# CowHeater_SCH.net
KiCad netlist of a schematic drawn in Altium Designer
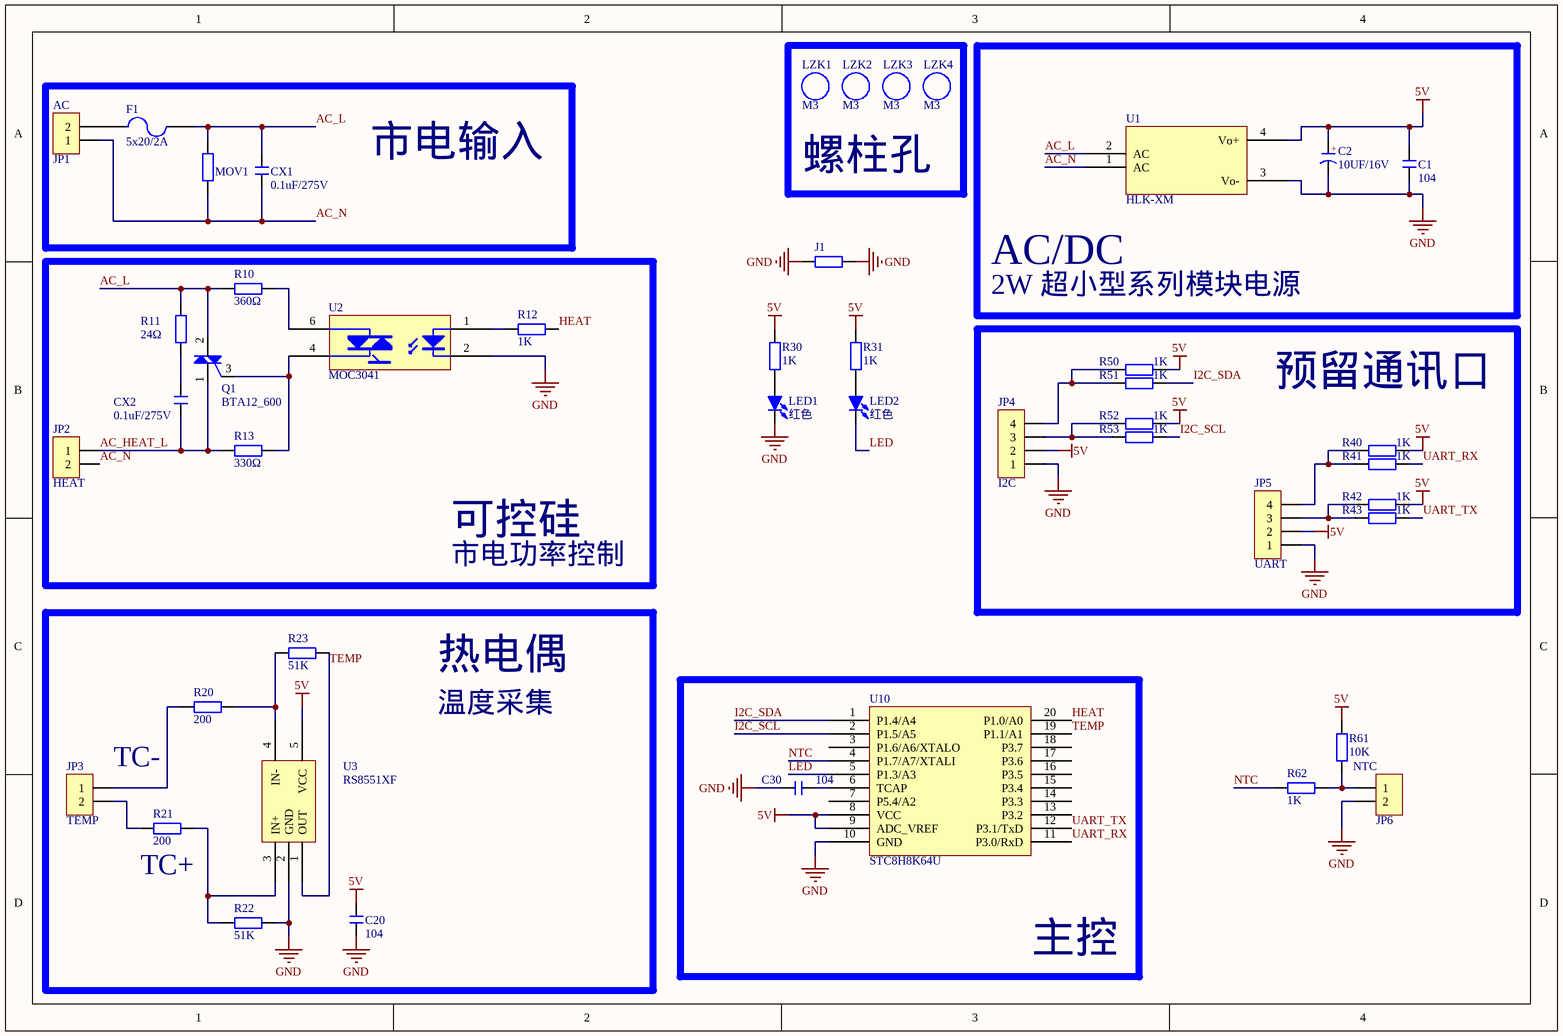
[diagram p0: CowHeater_SCH.SchDoc]

(export (version "E")
  (design (tool "Eeschema 10.0.6"))
  (components
    (comp (ref "C1")
      (value "104")
      (footprint "C 0603")
      (description "无极性贴片电容")
      (fields (field (name "版权归属") "源创客"))
      (libsource (lib "电阻-电容-电感") (part "C"))
    )
    (comp (ref "C2")
      (value "10UF/16V")
      (footprint "CAP 3.5*8*11.5")
      (description "直插电解电容")
      (fields (field (name "版权归属") "源创客"))
      (libsource (lib "电阻-电容-电感") (part "C-CAP"))
    )
    (comp (ref "C20")
      (value "104")
      (footprint "C 0603")
      (description "无极性贴片电容")
      (fields (field (name "版权归属") "源创客"))
      (libsource (lib "电阻-电容-电感") (part "C"))
    )
    (comp (ref "C30")
      (value "104")
      (footprint "C 0603")
      (description "无极性贴片电容")
      (fields (field (name "版权归属") "源创客"))
      (libsource (lib "电阻-电容-电感") (part "C"))
    )
    (comp (ref "CX1")
      (value "0.1uF/275V")
      (footprint "CX 10*13*11")
      (description "X电容")
      (fields (field (name "版权归属") "源创客"))
      (libsource (lib "电阻-电容-电感") (part "C-CX"))
    )
    (comp (ref "CX2")
      (value "0.1uF/275V")
      (footprint "CX 10*13*11")
      (description "X电容")
      (fields (field (name "版权归属") "源创客"))
      (libsource (lib "电阻-电容-电感") (part "C-CX"))
    )
    (comp (ref "F1")
      (value "5x20/2A")
      (footprint "FU BLX-A")
      (description "5*20保险丝")
      (fields (field (name "版权归属") "源创客"))
      (libsource (lib "保险丝-晶振") (part "FU 5x20"))
    )
    (comp (ref "J1")
      (value "1K")
      (footprint "R 0603")
      (description "贴片电阻")
      (fields (field (name "版权归属") "源创客"))
      (libsource (lib "电阻-电容-电感") (part "R"))
    )
    (comp (ref "JP1")
      (value "AC")
      (footprint "KF7620-2P")
      (description "2P接插件")
      (fields (field (name "版权归属") "源创客"))
      (libsource (lib "") (part "Header 2_2"))
    )
    (comp (ref "JP2")
      (value "HEAT")
      (footprint "KF7620-2P")
      (description "2P接插件")
      (fields (field (name "版权归属") "源创客"))
      (libsource (lib "") (part "Header 2_1"))
    )
    (comp (ref "JP3")
      (value "TEMP")
      (footprint "KF301-2P")
      (description "2P接插件")
      (fields (field (name "版权归属") "源创客"))
      (libsource (lib "") (part "Header 2_1"))
    )
    (comp (ref "JP4")
      (value "I2C")
      (footprint "XH2.54-4P")
      (description "4P接插件")
      (fields (field (name "版权归属") "源创客"))
      (libsource (lib "接插件") (part "Header 4"))
    )
    (comp (ref "JP5")
      (value "UART")
      (footprint "XH2.54-4P")
      (description "4P接插件")
      (fields (field (name "版权归属") "源创客"))
      (libsource (lib "接插件") (part "Header 4"))
    )
    (comp (ref "JP6")
      (value "NTC")
      (footprint "XH2.54-2P")
      (description "2P接插件")
      (fields (field (name "版权归属") "源创客"))
      (libsource (lib "接插件") (part "Header 2"))
    )
    (comp (ref "LED1")
      (value "红色")
      (footprint "LED 0603W")
      (description "贴片LED")
      (fields (field (name "版权归属") "源创客"))
      (libsource (lib "LED") (part "LED-SMD"))
    )
    (comp (ref "LED2")
      (value "红色")
      (footprint "LED 0603W")
      (description "贴片LED")
      (fields (field (name "版权归属") "源创客"))
      (libsource (lib "LED") (part "LED-SMD"))
    )
    (comp (ref "LZK1")
      (value "M3")
      (footprint "M3 125X300")
      (description "铜柱孔")
      (fields (field (name "版权归属") "源创客"))
      (libsource (lib "未分类器件") (part "M3"))
    )
    (comp (ref "LZK2")
      (value "M3")
      (footprint "M3 125X300")
      (description "铜柱孔")
      (fields (field (name "版权归属") "源创客"))
      (libsource (lib "未分类器件") (part "M3"))
    )
    (comp (ref "LZK3")
      (value "M3")
      (footprint "M3 125X300")
      (description "铜柱孔")
      (fields (field (name "版权归属") "源创客"))
      (libsource (lib "未分类器件") (part "M3"))
    )
    (comp (ref "LZK4")
      (value "M3")
      (footprint "M3 125X300")
      (description "铜柱孔")
      (fields (field (name "版权归属") "源创客"))
      (libsource (lib "未分类器件") (part "M3"))
    )
    (comp (ref "MOV1")
      (value "1K")
      (footprint "PcbLib1:RES-10-561(TVR)")
      (description "压敏电阻")
      (fields (field (name "版权归属") "源创客"))
      (libsource (lib "Schlib1") (part "MOV"))
    )
    (comp (ref "Q1")
      (value "BTA12_600")
      (footprint "PcbLib1:TO220_OUT5")
      (description "双向可控硅")
      (fields (field (name "版权归属") "源创客"))
      (libsource (lib "Schlib1") (part "BTA12_600"))
    )
    (comp (ref "R10")
      (value "360Ω")
      (footprint "RS 1W-F5")
      (description "直插色环电阻")
      (fields (field (name "版权归属") "源创客"))
      (libsource (lib "电阻-电容-电感") (part "R-CRR"))
    )
    (comp (ref "R11")
      (value "24Ω")
      (footprint "RS 1W-F5")
      (description "直插色环电阻")
      (fields (field (name "版权归属") "源创客"))
      (libsource (lib "电阻-电容-电感") (part "R-CRR"))
    )
    (comp (ref "R12")
      (value "1K")
      (footprint "R 0603")
      (description "贴片电阻")
      (fields (field (name "版权归属") "源创客"))
      (libsource (lib "电阻-电容-电感") (part "R"))
    )
    (comp (ref "R13")
      (value "330Ω")
      (footprint "RS 1W-F5")
      (description "直插色环电阻")
      (fields (field (name "版权归属") "源创客"))
      (libsource (lib "电阻-电容-电感") (part "R-CRR"))
    )
    (comp (ref "R20")
      (value "200")
      (footprint "R 0603")
      (description "贴片电阻")
      (fields (field (name "版权归属") "源创客"))
      (libsource (lib "电阻-电容-电感") (part "R"))
    )
    (comp (ref "R21")
      (value "200")
      (footprint "R 0603")
      (description "贴片电阻")
      (fields (field (name "版权归属") "源创客"))
      (libsource (lib "电阻-电容-电感") (part "R"))
    )
    (comp (ref "R22")
      (value "51K")
      (footprint "R 0603")
      (description "贴片电阻")
      (fields (field (name "版权归属") "源创客"))
      (libsource (lib "电阻-电容-电感") (part "R"))
    )
    (comp (ref "R23")
      (value "51K")
      (footprint "R 0603")
      (description "贴片电阻")
      (fields (field (name "版权归属") "源创客"))
      (libsource (lib "电阻-电容-电感") (part "R"))
    )
    (comp (ref "R30")
      (value "1K")
      (footprint "R 0603")
      (description "贴片电阻")
      (fields (field (name "版权归属") "源创客"))
      (libsource (lib "电阻-电容-电感") (part "R"))
    )
    (comp (ref "R31")
      (value "1K")
      (footprint "R 0603")
      (description "贴片电阻")
      (fields (field (name "版权归属") "源创客"))
      (libsource (lib "电阻-电容-电感") (part "R"))
    )
    (comp (ref "R40")
      (value "1K")
      (footprint "R 0603")
      (description "贴片电阻")
      (fields (field (name "版权归属") "源创客"))
      (libsource (lib "电阻-电容-电感") (part "R"))
    )
    (comp (ref "R41")
      (value "1K")
      (footprint "R 0603")
      (description "贴片电阻")
      (fields (field (name "版权归属") "源创客"))
      (libsource (lib "电阻-电容-电感") (part "R"))
    )
    (comp (ref "R42")
      (value "1K")
      (footprint "R 0603")
      (description "贴片电阻")
      (fields (field (name "版权归属") "源创客"))
      (libsource (lib "电阻-电容-电感") (part "R"))
    )
    (comp (ref "R43")
      (value "1K")
      (footprint "R 0603")
      (description "贴片电阻")
      (fields (field (name "版权归属") "源创客"))
      (libsource (lib "电阻-电容-电感") (part "R"))
    )
    (comp (ref "R50")
      (value "1K")
      (footprint "R 0603")
      (description "贴片电阻")
      (fields (field (name "版权归属") "源创客"))
      (libsource (lib "电阻-电容-电感") (part "R"))
    )
    (comp (ref "R51")
      (value "1K")
      (footprint "R 0603")
      (description "贴片电阻")
      (fields (field (name "版权归属") "源创客"))
      (libsource (lib "电阻-电容-电感") (part "R"))
    )
    (comp (ref "R52")
      (value "1K")
      (footprint "R 0603")
      (description "贴片电阻")
      (fields (field (name "版权归属") "源创客"))
      (libsource (lib "电阻-电容-电感") (part "R"))
    )
    (comp (ref "R53")
      (value "1K")
      (footprint "R 0603")
      (description "贴片电阻")
      (fields (field (name "版权归属") "源创客"))
      (libsource (lib "电阻-电容-电感") (part "R"))
    )
    (comp (ref "R61")
      (value "10K")
      (footprint "R 0603")
      (description "贴片电阻")
      (fields (field (name "版权归属") "源创客"))
      (libsource (lib "电阻-电容-电感") (part "R"))
    )
    (comp (ref "R62")
      (value "1K")
      (footprint "R 0603")
      (description "贴片电阻")
      (fields (field (name "版权归属") "源创客"))
      (libsource (lib "电阻-电容-电感") (part "R"))
    )
    (comp (ref "U1")
      (value "HLK-XM")
      (footprint "PcbLib1:HLK_5M")
      (description "超小型系列模块电源")
      (libsource (lib "Schlib1") (part "HLK-XM"))
    )
    (comp (ref "U2") (value "MOC3041") (footprint "DIP6-300") (libsource (lib "Schlib1") (part "MOC3041")))
    (comp (ref "U3")
      (value "RS8551XF")
      (footprint "SOT:SOT23-5N")
      (description "零漂移,1uV Vos,4.5MHz,1通道运放")
      (libsource (lib "Schlib1") (part "RS8551XF"))
    )
    (comp (ref "U10")
      (value "STC8H8K64U")
      (footprint "TSSOP:TSSOP20_N")
      (libsource (lib "Schlib1") (part "STC8H8K64U"))
    )
  )
  (nets
    (net (code "1") (name "/AC_HEAT_L") (class "Default")
      (node (ref "CX2") (pin "1") (pinfunction "1_1") (pintype "passive"))
      (node (ref "JP2") (pin "1") (pinfunction "1_1") (pintype "passive"))
      (node (ref "Q1") (pin "1") (pinfunction "A2_1") (pintype "passive"))
      (node (ref "R13") (pin "1") (pinfunction "1_1") (pintype "passive"))
    )
    (net (code "2") (name "/AC_L") (class "Default")
      (node (ref "CX1") (pin "1") (pinfunction "1_1") (pintype "passive"))
      (node (ref "F1") (pin "2") (pinfunction "2_2") (pintype "passive"))
      (node (ref "MOV1") (pin "2") (pinfunction "2_2") (pintype "passive"))
      (node (ref "Q1") (pin "2") (pinfunction "A1_2") (pintype "passive"))
      (node (ref "R10") (pin "1") (pinfunction "1_1") (pintype "passive"))
      (node (ref "R11") (pin "2") (pinfunction "2_2") (pintype "passive"))
      (node (ref "U1") (pin "2") (pinfunction "AC_2") (pintype "passive"))
    )
    (net (code "3") (name "/AC_N") (class "Default")
      (node (ref "CX1") (pin "2") (pinfunction "2_2") (pintype "passive"))
      (node (ref "JP1") (pin "1") (pinfunction "1_1") (pintype "passive"))
      (node (ref "JP2") (pin "2") (pinfunction "2_2") (pintype "passive"))
      (node (ref "MOV1") (pin "1") (pinfunction "1_1") (pintype "passive"))
      (node (ref "U1") (pin "1") (pinfunction "AC_1") (pintype "passive"))
    )
    (net (code "4") (name "/HEAT") (class "Default")
      (node (ref "R12") (pin "2") (pinfunction "2_2") (pintype "passive"))
      (node (ref "U10") (pin "20") (pinfunction "P1.0/A0_20") (pintype "passive"))
    )
    (net (code "5") (name "/I2C_SCL") (class "Default")
      (node (ref "R53") (pin "1") (pinfunction "1_1") (pintype "passive"))
      (node (ref "U10") (pin "2") (pinfunction "P1.5/A5_2") (pintype "passive"))
    )
    (net (code "6") (name "/I2C_SDA") (class "Default")
      (node (ref "R51") (pin "1") (pinfunction "1_1") (pintype "passive"))
      (node (ref "U10") (pin "1") (pinfunction "P1.4/A4_1") (pintype "passive"))
    )
    (net (code "7") (name "/LED") (class "Default")
      (node (ref "LED2") (pin "2") (pinfunction "K_2") (pintype "passive"))
      (node (ref "U10") (pin "5") (pinfunction "P1.3/A3_5") (pintype "passive"))
    )
    (net (code "8") (name "/NTC") (class "Default")
      (node (ref "R62") (pin "1") (pinfunction "1_1") (pintype "passive"))
      (node (ref "U10") (pin "4") (pinfunction "P1.7/A7/XTALI_4") (pintype "passive"))
    )
    (net (code "9") (name "/TEMP") (class "Default")
      (node (ref "R23") (pin "2") (pinfunction "2_2") (pintype "passive"))
      (node (ref "U10") (pin "19") (pinfunction "P1.1/A1_19") (pintype "passive"))
      (node (ref "U3") (pin "1") (pinfunction "OUT_1") (pintype "passive"))
    )
    (net (code "10") (name "/UART_RX") (class "Default")
      (node (ref "R41") (pin "1") (pinfunction "1_1") (pintype "passive"))
      (node (ref "U10") (pin "11") (pinfunction "P3.0/RxD_11") (pintype "passive"))
    )
    (net (code "11") (name "/UART_TX") (class "Default")
      (node (ref "R43") (pin "1") (pinfunction "1_1") (pintype "passive"))
      (node (ref "U10") (pin "12") (pinfunction "P3.1/TxD_12") (pintype "passive"))
    )
    (net (code "12") (name "5V") (class "Default")
      (node (ref "C1") (pin "2") (pinfunction "2_2") (pintype "passive"))
      (node (ref "C2") (pin "1") (pinfunction "A_1") (pintype "passive"))
      (node (ref "C20") (pin "2") (pinfunction "2_2") (pintype "passive"))
      (node (ref "JP4") (pin "2") (pinfunction "2_2") (pintype "passive"))
      (node (ref "JP5") (pin "2") (pinfunction "2_2") (pintype "passive"))
      (node (ref "R30") (pin "2") (pinfunction "2_2") (pintype "passive"))
      (node (ref "R31") (pin "2") (pinfunction "2_2") (pintype "passive"))
      (node (ref "R40") (pin "1") (pinfunction "1_1") (pintype "passive"))
      (node (ref "R42") (pin "1") (pinfunction "1_1") (pintype "passive"))
      (node (ref "R50") (pin "1") (pinfunction "1_1") (pintype "passive"))
      (node (ref "R52") (pin "1") (pinfunction "1_1") (pintype "passive"))
      (node (ref "R61") (pin "1") (pinfunction "1_1") (pintype "passive"))
      (node (ref "U1") (pin "4") (pinfunction "Vo+_4") (pintype "passive"))
      (node (ref "U10") (pin "8") (pinfunction "VCC_8") (pintype "passive"))
      (node (ref "U10") (pin "9") (pinfunction "ADC_VREF_9") (pintype "passive"))
      (node (ref "U3") (pin "5") (pinfunction "VCC_5") (pintype "passive"))
    )
    (net (code "13") (name "GND") (class "Default")
      (node (ref "C1") (pin "1") (pinfunction "1_1") (pintype "passive"))
      (node (ref "C2") (pin "2") (pinfunction "K_2") (pintype "passive"))
      (node (ref "C20") (pin "1") (pinfunction "1_1") (pintype "passive"))
      (node (ref "C30") (pin "2") (pinfunction "2_2") (pintype "passive"))
      (node (ref "J1") (pin "1") (pinfunction "1_1") (pintype "passive"))
      (node (ref "J1") (pin "2") (pinfunction "2_2") (pintype "passive"))
      (node (ref "JP4") (pin "1") (pinfunction "1_1") (pintype "passive"))
      (node (ref "JP5") (pin "1") (pinfunction "1_1") (pintype "passive"))
      (node (ref "JP6") (pin "2") (pinfunction "2_2") (pintype "passive"))
      (node (ref "LED1") (pin "2") (pinfunction "K_2") (pintype "passive"))
      (node (ref "R22") (pin "2") (pinfunction "2_2") (pintype "passive"))
      (node (ref "U1") (pin "3") (pinfunction "Vo-_3") (pintype "passive"))
      (node (ref "U10") (pin "10") (pinfunction "GND_10") (pintype "passive"))
      (node (ref "U2") (pin "2") (pintype "passive"))
      (node (ref "U3") (pin "2") (pinfunction "GND_2") (pintype "passive"))
    )
    (net (code "14") (name "Net-(CX2-Pad2)") (class "Default")
      (node (ref "CX2") (pin "2") (pinfunction "2_2") (pintype "passive"))
      (node (ref "R11") (pin "1") (pinfunction "1_1") (pintype "passive"))
    )
    (net (code "15") (name "Net-(F1-Pad1)") (class "Default")
      (node (ref "F1") (pin "1") (pinfunction "1_1") (pintype "passive"))
      (node (ref "JP1") (pin "2") (pinfunction "2_2") (pintype "passive"))
    )
    (net (code "16") (name "Net-(JP3-Pad1)") (class "Default")
      (node (ref "JP3") (pin "1") (pinfunction "1_1") (pintype "passive"))
      (node (ref "R20") (pin "1") (pinfunction "1_1") (pintype "passive"))
    )
    (net (code "17") (name "Net-(JP3-Pad2)") (class "Default")
      (node (ref "JP3") (pin "2") (pinfunction "2_2") (pintype "passive"))
      (node (ref "R21") (pin "1") (pinfunction "1_1") (pintype "passive"))
    )
    (net (code "18") (name "Net-(JP4-Pad3)") (class "Default")
      (node (ref "JP4") (pin "3") (pinfunction "3_3") (pintype "passive"))
      (node (ref "R52") (pin "2") (pinfunction "2_2") (pintype "passive"))
      (node (ref "R53") (pin "2") (pinfunction "2_2") (pintype "passive"))
    )
    (net (code "19") (name "Net-(JP4-Pad4)") (class "Default")
      (node (ref "JP4") (pin "4") (pinfunction "4_4") (pintype "passive"))
      (node (ref "R50") (pin "2") (pinfunction "2_2") (pintype "passive"))
      (node (ref "R51") (pin "2") (pinfunction "2_2") (pintype "passive"))
    )
    (net (code "20") (name "Net-(JP5-Pad3)") (class "Default")
      (node (ref "JP5") (pin "3") (pinfunction "3_3") (pintype "passive"))
      (node (ref "R42") (pin "2") (pinfunction "2_2") (pintype "passive"))
      (node (ref "R43") (pin "2") (pinfunction "2_2") (pintype "passive"))
    )
    (net (code "21") (name "Net-(JP5-Pad4)") (class "Default")
      (node (ref "JP5") (pin "4") (pinfunction "4_4") (pintype "passive"))
      (node (ref "R40") (pin "2") (pinfunction "2_2") (pintype "passive"))
      (node (ref "R41") (pin "2") (pinfunction "2_2") (pintype "passive"))
    )
    (net (code "22") (name "Net-(JP6-Pad1)") (class "Default")
      (node (ref "JP6") (pin "1") (pinfunction "1_1") (pintype "passive"))
      (node (ref "R61") (pin "2") (pinfunction "2_2") (pintype "passive"))
      (node (ref "R62") (pin "2") (pinfunction "2_2") (pintype "passive"))
    )
    (net (code "23") (name "Net-(LED1-A)") (class "Default")
      (node (ref "LED1") (pin "1") (pinfunction "A_1") (pintype "passive"))
      (node (ref "R30") (pin "1") (pinfunction "1_1") (pintype "passive"))
    )
    (net (code "24") (name "Net-(LED2-A)") (class "Default")
      (node (ref "LED2") (pin "1") (pinfunction "A_1") (pintype "passive"))
      (node (ref "R31") (pin "1") (pinfunction "1_1") (pintype "passive"))
    )
    (net (code "25") (name "Net-(Q1-G)") (class "Default")
      (node (ref "Q1") (pin "3") (pinfunction "G_3") (pintype "passive"))
      (node (ref "R13") (pin "2") (pinfunction "2_2") (pintype "passive"))
      (node (ref "U2") (pin "4") (pintype "passive"))
    )
    (net (code "26") (name "Net-(R10-Pad2)") (class "Default")
      (node (ref "R10") (pin "2") (pinfunction "2_2") (pintype "passive"))
      (node (ref "U2") (pin "6") (pintype "passive"))
    )
    (net (code "27") (name "Net-(R12-Pad1)") (class "Default")
      (node (ref "R12") (pin "1") (pinfunction "1_1") (pintype "passive"))
      (node (ref "U2") (pin "1") (pintype "passive"))
    )
    (net (code "28") (name "Net-(U3-IN+)") (class "Default")
      (node (ref "R21") (pin "2") (pinfunction "2_2") (pintype "passive"))
      (node (ref "R22") (pin "1") (pinfunction "1_1") (pintype "passive"))
      (node (ref "U3") (pin "3") (pinfunction "IN+_3") (pintype "passive"))
    )
    (net (code "29") (name "Net-(U3-IN-)") (class "Default")
      (node (ref "R20") (pin "2") (pinfunction "2_2") (pintype "passive"))
      (node (ref "R23") (pin "1") (pinfunction "1_1") (pintype "passive"))
      (node (ref "U3") (pin "4") (pinfunction "IN-_4") (pintype "passive"))
    )
    (net (code "30") (name "Net-(U10-TCAP)") (class "Default")
      (node (ref "C30") (pin "1") (pinfunction "1_1") (pintype "passive"))
      (node (ref "U10") (pin "6") (pinfunction "TCAP_6") (pintype "passive"))
    )
    (net (code "31") (name "unconnected-(U10-P1.6{slash}A6{slash}XTALO-Pad3)") (class "Default")
      (node (ref "U10") (pin "3") (pinfunction "P1.6/A6/XTALO_3") (pintype "passive"))
    )
    (net (code "32") (name "unconnected-(U10-P3.2-Pad13)") (class "Default")
      (node (ref "U10") (pin "13") (pinfunction "P3.2_13") (pintype "passive"))
    )
    (net (code "33") (name "unconnected-(U10-P3.3-Pad14)") (class "Default")
      (node (ref "U10") (pin "14") (pinfunction "P3.3_14") (pintype "passive"))
    )
    (net (code "34") (name "unconnected-(U10-P3.4-Pad15)") (class "Default")
      (node (ref "U10") (pin "15") (pinfunction "P3.4_15") (pintype "passive"))
    )
    (net (code "35") (name "unconnected-(U10-P3.5-Pad16)") (class "Default")
      (node (ref "U10") (pin "16") (pinfunction "P3.5_16") (pintype "passive"))
    )
    (net (code "36") (name "unconnected-(U10-P3.6-Pad17)") (class "Default")
      (node (ref "U10") (pin "17") (pinfunction "P3.6_17") (pintype "passive"))
    )
    (net (code "37") (name "unconnected-(U10-P3.7-Pad18)") (class "Default")
      (node (ref "U10") (pin "18") (pinfunction "P3.7_18") (pintype "passive"))
    )
    (net (code "38") (name "unconnected-(U10-P5.4{slash}A2-Pad7)") (class "Default")
      (node (ref "U10") (pin "7") (pinfunction "P5.4/A2_7") (pintype "passive"))
    )
  )
)
